# ESP32.net
KiCad netlist of a schematic drawn in Altium Designer
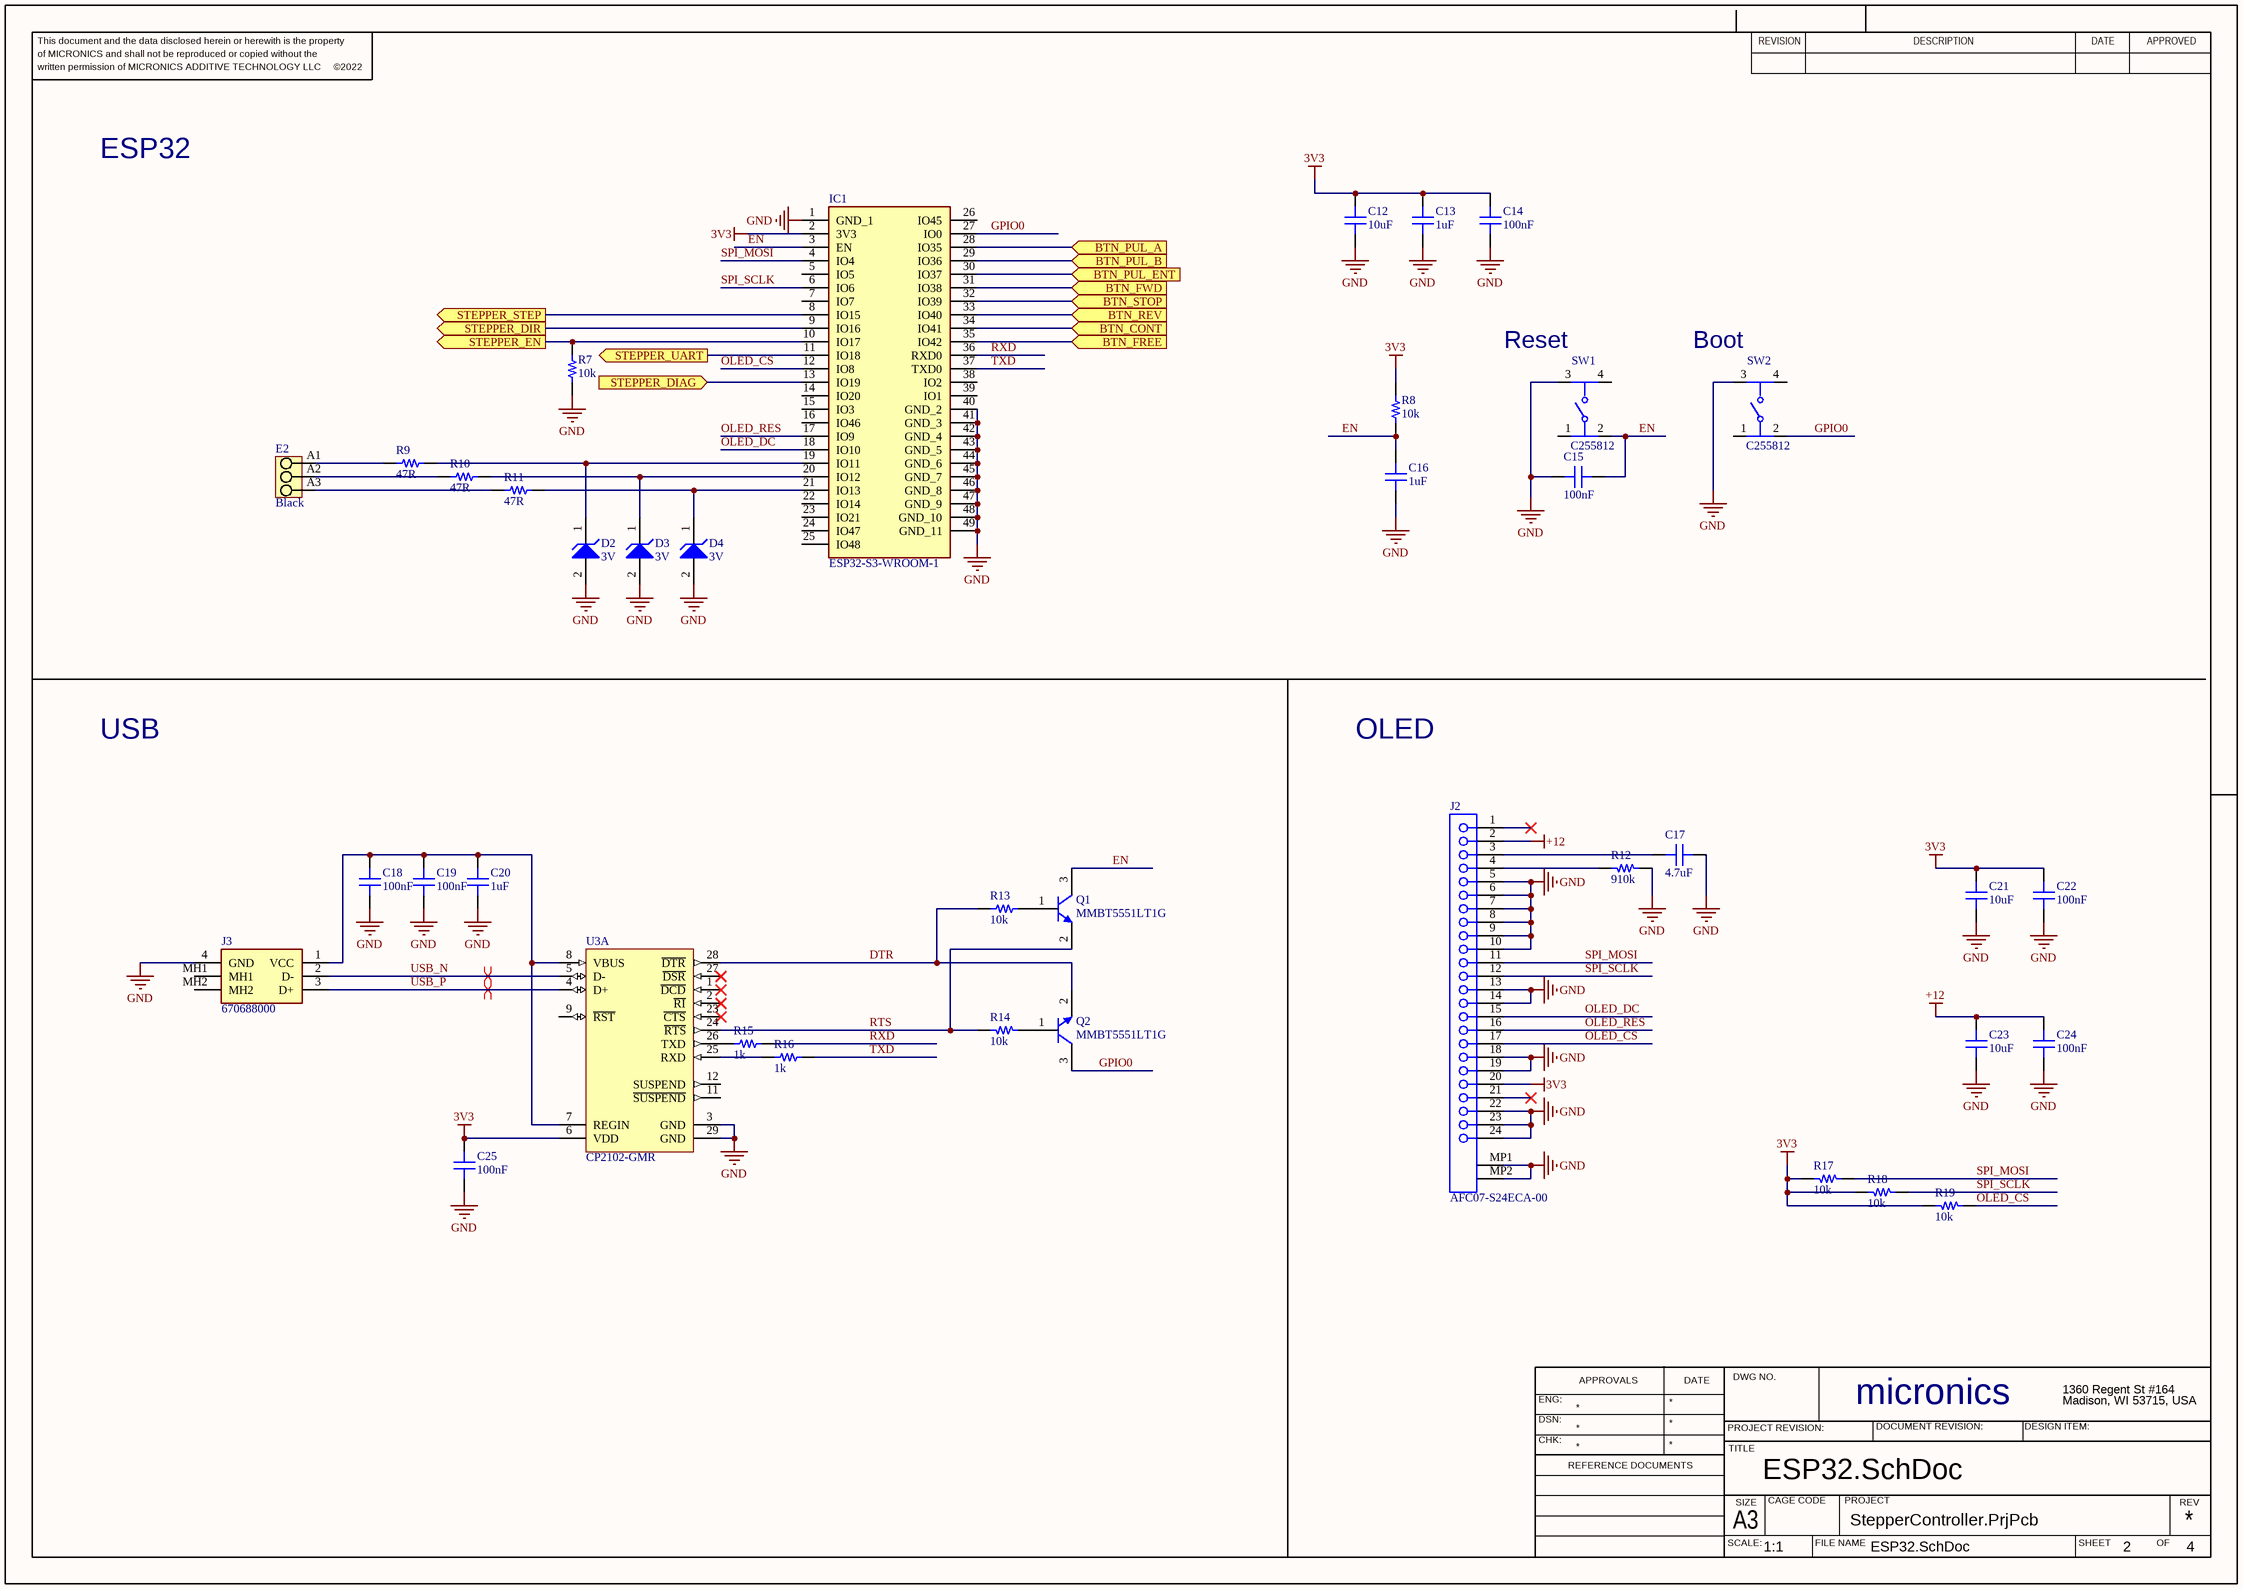
[diagram p0: ESP32.SchDoc]

(export (version "E")
  (design (tool "Eeschema 10.0.6"))
  (components
    (comp (ref "C12")
      (value "10uF")
      (footprint "CAP 1206_3216 - 0.8MM")
      (description "C89632")
      (fields (field (name "PART NUMBER") "MM061A101JCT2A") (field (name "MANUFACTURER") "AVX Corporation"))
      (libsource (lib "Celestial Altium Library - altium_library") (part "Capacitor"))
    )
    (comp (ref "C13")
      (value "1uF")
      (footprint "CAP 0603_1608")
      (description "C15849")
      (fields
        (field (name "PART NUMBER") "250X14W223MV4T")
        (field (name "MANUFACTURER") "Johanson Dielectrics Inc.")
      )
      (libsource (lib "Celestial Altium Library - altium_library") (part "Capacitor"))
    )
    (comp (ref "C14")
      (value "100nF")
      (footprint "CAP 0603_1608")
      (description "C14663")
      (fields
        (field (name "PART NUMBER") "250X14W223MV4T")
        (field (name "MANUFACTURER") "Johanson Dielectrics Inc.")
      )
      (libsource (lib "Celestial Altium Library - altium_library") (part "Capacitor"))
    )
    (comp (ref "C15")
      (value "100nF")
      (footprint "CAP 0603_1608")
      (description "C14663")
      (fields
        (field (name "PART NUMBER") "250X14W223MV4T")
        (field (name "MANUFACTURER") "Johanson Dielectrics Inc.")
      )
      (libsource (lib "Celestial Altium Library - altium_library") (part "Capacitor"))
    )
    (comp (ref "C16")
      (value "1uF")
      (footprint "CAP 0603_1608")
      (description "C15849")
      (fields
        (field (name "PART NUMBER") "250X14W223MV4T")
        (field (name "MANUFACTURER") "Johanson Dielectrics Inc.")
      )
      (libsource (lib "Celestial Altium Library - altium_library") (part "Capacitor"))
    )
    (comp (ref "C17")
      (value "4.7uF")
      (footprint "CAP 1206_3216 - 0.8MM")
      (description "C29823")
      (fields (field (name "PART NUMBER") "MM061A101JCT2A") (field (name "MANUFACTURER") "AVX Corporation"))
      (libsource (lib "Celestial Altium Library - altium_library") (part "Capacitor"))
    )
    (comp (ref "C18")
      (value "100nF")
      (footprint "CAP 0603_1608")
      (description "C14663")
      (fields
        (field (name "PART NUMBER") "250X14W223MV4T")
        (field (name "MANUFACTURER") "Johanson Dielectrics Inc.")
      )
      (libsource (lib "Celestial Altium Library - altium_library") (part "Capacitor"))
    )
    (comp (ref "C19")
      (value "100nF")
      (footprint "CAP 0603_1608")
      (description "C14663")
      (fields
        (field (name "PART NUMBER") "250X14W223MV4T")
        (field (name "MANUFACTURER") "Johanson Dielectrics Inc.")
      )
      (libsource (lib "Celestial Altium Library - altium_library") (part "Capacitor"))
    )
    (comp (ref "C20")
      (value "1uF")
      (footprint "CAP 0603_1608")
      (description "C15849")
      (fields
        (field (name "PART NUMBER") "250X14W223MV4T")
        (field (name "MANUFACTURER") "Johanson Dielectrics Inc.")
      )
      (libsource (lib "Celestial Altium Library - altium_library") (part "Capacitor"))
    )
    (comp (ref "C21")
      (value "10uF")
      (footprint "CAP 1206_3216 - 0.8MM")
      (description "C89632")
      (fields (field (name "PART NUMBER") "MM061A101JCT2A") (field (name "MANUFACTURER") "AVX Corporation"))
      (libsource (lib "Celestial Altium Library - altium_library") (part "Capacitor"))
    )
    (comp (ref "C22")
      (value "100nF")
      (footprint "CAP 0603_1608")
      (description "C14663")
      (fields
        (field (name "PART NUMBER") "250X14W223MV4T")
        (field (name "MANUFACTURER") "Johanson Dielectrics Inc.")
      )
      (libsource (lib "Celestial Altium Library - altium_library") (part "Capacitor"))
    )
    (comp (ref "C23")
      (value "10uF")
      (footprint "CAP 1206_3216 - 0.8MM")
      (description "C89632")
      (fields (field (name "PART NUMBER") "MM061A101JCT2A") (field (name "MANUFACTURER") "AVX Corporation"))
      (libsource (lib "Celestial Altium Library - altium_library") (part "Capacitor"))
    )
    (comp (ref "C24")
      (value "100nF")
      (footprint "CAP 0603_1608")
      (description "C14663")
      (fields
        (field (name "PART NUMBER") "250X14W223MV4T")
        (field (name "MANUFACTURER") "Johanson Dielectrics Inc.")
      )
      (libsource (lib "Celestial Altium Library - altium_library") (part "Capacitor"))
    )
    (comp (ref "C25")
      (value "100nF")
      (footprint "CAP 0603_1608")
      (description "C14663")
      (fields
        (field (name "PART NUMBER") "250X14W223MV4T")
        (field (name "MANUFACTURER") "Johanson Dielectrics Inc.")
      )
      (libsource (lib "Celestial Altium Library - altium_library") (part "Capacitor"))
    )
    (comp (ref "D2")
      (value "3V")
      (footprint "ONSC-SOD-123-2-425-04_V")
      (description "C12756")
      (fields (field (name "PARTNUMBER") "SZMMSZ12T3G") (field (name "MANUFACTURER") "On Semiconductor"))
      (libsource (lib "Altium Content Vault") (part "ONSC-K1A2-2"))
    )
    (comp (ref "D3")
      (value "3V")
      (footprint "ONSC-SOD-123-2-425-04_V")
      (description "C12756")
      (fields (field (name "PARTNUMBER") "SZMMSZ12T3G") (field (name "MANUFACTURER") "On Semiconductor"))
      (libsource (lib "Altium Content Vault") (part "ONSC-K1A2-2"))
    )
    (comp (ref "D4")
      (value "3V")
      (footprint "ONSC-SOD-123-2-425-04_V")
      (description "C12756")
      (fields (field (name "PARTNUMBER") "SZMMSZ12T3G") (field (name "MANUFACTURER") "On Semiconductor"))
      (libsource (lib "Altium Content Vault") (part "ONSC-K1A2-2"))
    )
    (comp (ref "E2")
      (value "Black")
      (footprint "PM_5_08_90_03")
      (description "C430602")
      (fields (field (name "PARTNUMBER") "1760500000") (field (name "MANUFACTURER") "Weidmueller"))
      (libsource (lib "Altium Content Vault") (part "Terminal_03_1x03"))
    )
    (comp (ref "IC1")
      (value "ESP32-S3-WROOM-1")
      (footprint "SamacSys:ESP32S3WROOM1")
      (description "Integrated Circuit")
      (libsource (lib "*") (part "ESP32-S3-WROOM-1"))
    )
    (comp (ref "J2")
      (value "AFC07-S24ECA-00")
      (footprint "MOLX-52437-2471")
      (description "C262643")
      (fields (field (name "PARTNUMBER") "52437-2471") (field (name "MANUFACTURER") "Molex"))
      (libsource (lib "Altium Content Vault") (part "MOLX-52437-2471"))
    )
    (comp (ref "J3")
      (value "670688000")
      (footprint "SamacSys:670688000")
      (description "Connector")
      (fields
        (field (name "MANUFACTURER_PART_NUMBER") "67068-8000")
        (field (name "MOUSER PART NUMBER") "538-67068-8000")
      )
      (libsource (lib "SamacSys") (part "67068-8000"))
    )
    (comp (ref "Q1")
      (value "MMBT5551LT1G")
      (footprint "ONSC-SOT-23-3-318-08_V")
      (description "C41095")
      (fields (field (name "MANUFACTURER") "On Semiconductor"))
      (libsource (lib "Altium Content Vault") (part "ONSC-NPN-B1E2C3-3"))
    )
    (comp (ref "Q2")
      (value "MMBT5551LT1G")
      (footprint "ONSC-SOT-23-3-318-08_V")
      (description "C41095")
      (fields (field (name "MANUFACTURER") "On Semiconductor"))
      (libsource (lib "Altium Content Vault") (part "ONSC-NPN-B1E2C3-3"))
    )
    (comp (ref "R7")
      (value "10k")
      (footprint "RES 0603_1608")
      (description "RES 1% 0603")
      (fields
        (field (name "PART NUMBER") "RNCF0603DTE23K2")
        (field (name "MANUFACTURER") "Stackpole Electronics Inc")
      )
      (libsource (lib "Celestial Altium Library - altium_library") (part "Resistor"))
    )
    (comp (ref "R8")
      (value "10k")
      (footprint "RES 0603_1608")
      (description "RES 1% 0603")
      (fields
        (field (name "PART NUMBER") "RNCF0603DTE23K2")
        (field (name "MANUFACTURER") "Stackpole Electronics Inc")
      )
      (libsource (lib "Celestial Altium Library - altium_library") (part "Resistor"))
    )
    (comp (ref "R9")
      (value "47R")
      (footprint "RES 0603_1608")
      (description "RES 1% 0603")
      (fields
        (field (name "PART NUMBER") "RNCF0603DTE23K2")
        (field (name "MANUFACTURER") "Stackpole Electronics Inc")
      )
      (libsource (lib "Celestial Altium Library - altium_library") (part "Resistor"))
    )
    (comp (ref "R10")
      (value "47R")
      (footprint "RES 0603_1608")
      (description "RES 1% 0603")
      (fields
        (field (name "PART NUMBER") "RNCF0603DTE23K2")
        (field (name "MANUFACTURER") "Stackpole Electronics Inc")
      )
      (libsource (lib "Celestial Altium Library - altium_library") (part "Resistor"))
    )
    (comp (ref "R11")
      (value "47R")
      (footprint "RES 0603_1608")
      (description "RES 1% 0603")
      (fields
        (field (name "PART NUMBER") "RNCF0603DTE23K2")
        (field (name "MANUFACTURER") "Stackpole Electronics Inc")
      )
      (libsource (lib "Celestial Altium Library - altium_library") (part "Resistor"))
    )
    (comp (ref "R12")
      (value "910k")
      (footprint "RES 0603_1608")
      (description "RES 1% 0603")
      (fields
        (field (name "PART NUMBER") "RNCS0603BKE10K0")
        (field (name "MANUFACTURER") "Stackpole Electronics Inc")
      )
      (libsource (lib "Celestial Altium Library - altium_library") (part "Resistor"))
    )
    (comp (ref "R13")
      (value "10k")
      (footprint "RES 0603_1608")
      (description "RES 1% 0603")
      (fields
        (field (name "PART NUMBER") "RNCF0603DTE23K2")
        (field (name "MANUFACTURER") "Stackpole Electronics Inc")
      )
      (libsource (lib "Celestial Altium Library - altium_library") (part "Resistor"))
    )
    (comp (ref "R14")
      (value "10k")
      (footprint "RES 0603_1608")
      (description "RES 1% 0603")
      (fields
        (field (name "PART NUMBER") "RNCF0603DTE23K2")
        (field (name "MANUFACTURER") "Stackpole Electronics Inc")
      )
      (libsource (lib "Celestial Altium Library - altium_library") (part "Resistor"))
    )
    (comp (ref "R15")
      (value "1k")
      (footprint "RES 0603_1608")
      (description "RES 1% 0603")
      (fields
        (field (name "PART NUMBER") "RNCF0603DTE23K2")
        (field (name "MANUFACTURER") "Stackpole Electronics Inc")
      )
      (libsource (lib "Celestial Altium Library - altium_library") (part "Resistor"))
    )
    (comp (ref "R16")
      (value "1k")
      (footprint "RES 0603_1608")
      (description "RES 1% 0603")
      (fields
        (field (name "PART NUMBER") "RNCF0603DTE23K2")
        (field (name "MANUFACTURER") "Stackpole Electronics Inc")
      )
      (libsource (lib "Celestial Altium Library - altium_library") (part "Resistor"))
    )
    (comp (ref "R17")
      (value "10k")
      (footprint "RES 0603_1608")
      (description "RES 1% 0603")
      (fields
        (field (name "PART NUMBER") "RNCF0603DTE23K2")
        (field (name "MANUFACTURER") "Stackpole Electronics Inc")
      )
      (libsource (lib "Celestial Altium Library - altium_library") (part "Resistor"))
    )
    (comp (ref "R18")
      (value "10k")
      (footprint "RES 0603_1608")
      (description "RES 1% 0603")
      (fields
        (field (name "PART NUMBER") "RNCF0603DTE23K2")
        (field (name "MANUFACTURER") "Stackpole Electronics Inc")
      )
      (libsource (lib "Celestial Altium Library - altium_library") (part "Resistor"))
    )
    (comp (ref "R19")
      (value "10k")
      (footprint "RES 0603_1608")
      (description "RES 1% 0603")
      (fields
        (field (name "PART NUMBER") "RNCF0603DTE23K2")
        (field (name "MANUFACTURER") "Stackpole Electronics Inc")
      )
      (libsource (lib "Celestial Altium Library - altium_library") (part "Resistor"))
    )
    (comp (ref "SW1")
      (value "C255812")
      (footprint "FP-FSM2JSMAA-MFG")
      (description "SWITCH TACTILE SPST-NO 0.05A 24V")
      (fields
        (field (name "MANUFACTURER PART NUMBER") "FSM2JSMAA")
        (field (name "MANUFACTURER") "TE Connectivity")
      )
      (libsource (lib "Altium Content Vault") (part "b8895f3f4cefb76e1819d2863dba89b"))
    )
    (comp (ref "SW2")
      (value "C255812")
      (footprint "FP-FSM2JSMAA-MFG")
      (description "SWITCH TACTILE SPST-NO 0.05A 24V")
      (fields
        (field (name "MANUFACTURER PART NUMBER") "FSM2JSMAA")
        (field (name "MANUFACTURER") "TE Connectivity")
      )
      (libsource (lib "Altium Content Vault") (part "b8895f3f4cefb76e1819d2863dba89b"))
    )
    (comp (ref "U3")
      (value "CP2102-GMR")
      (footprint "SLAB-QFN-28-3125x3125TP_M")
      (description "Single-Chip USB to URAT Bridge, 3.3 V, -40 to 85 degC, 28-Pin QFN, RoHS, Tape and Reel")
      (fields (field (name "MANUFACTURER") "Silicon Labs"))
      (libsource (lib "Altium Content Vault") (part "SLAB-CP210X-QFN-28-29"))
    )
  )
  (nets
    (net (code "1") (name "+12") (class "Default")
      (node (ref "C23") (pin "2") (pinfunction "2_2") (pintype "passive"))
      (node (ref "C24") (pin "1") (pinfunction "1_1") (pintype "passive"))
      (node (ref "J2") (pin "2") (pinfunction "2_2") (pintype "passive"))
    )
    (net (code "2") (name "/BTN_CONT") (class "Default")
      (node (ref "IC1") (pin "34") (pinfunction "IO41_34") (pintype "passive"))
    )
    (net (code "3") (name "/BTN_FREE") (class "Default")
      (node (ref "IC1") (pin "35") (pinfunction "IO42_35") (pintype "passive"))
    )
    (net (code "4") (name "/BTN_FWD") (class "Default")
      (node (ref "IC1") (pin "31") (pinfunction "IO38_31") (pintype "passive"))
    )
    (net (code "5") (name "/BTN_PUL_A") (class "Default")
      (node (ref "IC1") (pin "28") (pinfunction "IO35_28") (pintype "passive"))
    )
    (net (code "6") (name "/BTN_PUL_B") (class "Default")
      (node (ref "IC1") (pin "29") (pinfunction "IO36_29") (pintype "passive"))
    )
    (net (code "7") (name "/BTN_PUL_ENT") (class "Default")
      (node (ref "IC1") (pin "30") (pinfunction "IO37_30") (pintype "passive"))
    )
    (net (code "8") (name "/BTN_REV") (class "Default")
      (node (ref "IC1") (pin "33") (pinfunction "IO40_33") (pintype "passive"))
    )
    (net (code "9") (name "/BTN_STOP") (class "Default")
      (node (ref "IC1") (pin "32") (pinfunction "IO39_32") (pintype "passive"))
    )
    (net (code "10") (name "/DTR") (class "Default")
      (node (ref "Q2") (pin "2") (pinfunction "E_2") (pintype "passive"))
      (node (ref "R13") (pin "1") (pinfunction "1_1") (pintype "passive"))
      (node (ref "U3") (pin "28") (pinfunction "~{DTR}_28") (pintype "output"))
    )
    (net (code "11") (name "/EN") (class "Default")
      (node (ref "C15") (pin "1") (pinfunction "1_1") (pintype "passive"))
      (node (ref "C16") (pin "2") (pinfunction "2_2") (pintype "passive"))
      (node (ref "IC1") (pin "3") (pinfunction "EN_3") (pintype "passive"))
      (node (ref "Q1") (pin "3") (pinfunction "C_3") (pintype "passive"))
      (node (ref "R8") (pin "2") (pinfunction "2_2") (pintype "passive"))
      (node (ref "SW1") (pin "2") (pinfunction "2_2") (pintype "passive"))
    )
    (net (code "12") (name "/GPIO0") (class "Default")
      (node (ref "IC1") (pin "27") (pinfunction "IO0_27") (pintype "passive"))
      (node (ref "Q2") (pin "3") (pinfunction "C_3") (pintype "passive"))
      (node (ref "SW2") (pin "2") (pinfunction "2_2") (pintype "passive"))
    )
    (net (code "13") (name "/OLED_CS") (class "Default")
      (node (ref "IC1") (pin "12") (pinfunction "IO8_12") (pintype "passive"))
      (node (ref "J2") (pin "17") (pinfunction "17_17") (pintype "passive"))
      (node (ref "R19") (pin "1") (pinfunction "1_1") (pintype "passive"))
    )
    (net (code "14") (name "/OLED_DC") (class "Default")
      (node (ref "IC1") (pin "18") (pinfunction "IO10_18") (pintype "passive"))
      (node (ref "J2") (pin "15") (pinfunction "15_15") (pintype "passive"))
    )
    (net (code "15") (name "/OLED_RES") (class "Default")
      (node (ref "IC1") (pin "17") (pinfunction "IO9_17") (pintype "passive"))
      (node (ref "J2") (pin "16") (pinfunction "16_16") (pintype "passive"))
    )
    (net (code "16") (name "/RTS") (class "Default")
      (node (ref "Q1") (pin "2") (pinfunction "E_2") (pintype "passive"))
      (node (ref "R14") (pin "1") (pinfunction "1_1") (pintype "passive"))
      (node (ref "U3") (pin "24") (pinfunction "~{RTS}_24") (pintype "output"))
    )
    (net (code "17") (name "/RXD") (class "Default")
      (node (ref "IC1") (pin "36") (pinfunction "RXD0_36") (pintype "passive"))
      (node (ref "R15") (pin "2") (pinfunction "2_2") (pintype "passive"))
    )
    (net (code "18") (name "/SPI_MOSI") (class "Default")
      (node (ref "IC1") (pin "4") (pinfunction "IO4_4") (pintype "passive"))
      (node (ref "J2") (pin "11") (pinfunction "11_11") (pintype "passive"))
      (node (ref "R17") (pin "1") (pinfunction "1_1") (pintype "passive"))
    )
    (net (code "19") (name "/SPI_SCLK") (class "Default")
      (node (ref "IC1") (pin "6") (pinfunction "IO6_6") (pintype "passive"))
      (node (ref "J2") (pin "12") (pinfunction "12_12") (pintype "passive"))
      (node (ref "R18") (pin "1") (pinfunction "1_1") (pintype "passive"))
    )
    (net (code "20") (name "/STEPPER_DIAG") (class "Default")
      (node (ref "IC1") (pin "13") (pinfunction "IO19_13") (pintype "passive"))
    )
    (net (code "21") (name "/STEPPER_DIR") (class "Default")
      (node (ref "IC1") (pin "9") (pinfunction "IO16_9") (pintype "passive"))
    )
    (net (code "22") (name "/STEPPER_EN") (class "Default")
      (node (ref "IC1") (pin "10") (pinfunction "IO17_10") (pintype "passive"))
      (node (ref "R7") (pin "1") (pinfunction "1_1") (pintype "passive"))
    )
    (net (code "23") (name "/STEPPER_STEP") (class "Default")
      (node (ref "IC1") (pin "8") (pinfunction "IO15_8") (pintype "passive"))
    )
    (net (code "24") (name "/STEPPER_UART") (class "Default")
      (node (ref "IC1") (pin "11") (pinfunction "IO18_11") (pintype "passive"))
    )
    (net (code "25") (name "/TXD") (class "Default")
      (node (ref "IC1") (pin "37") (pinfunction "TXD0_37") (pintype "passive"))
      (node (ref "R16") (pin "2") (pinfunction "2_2") (pintype "passive"))
    )
    (net (code "26") (name "/USB_N") (class "Default")
      (node (ref "J3") (pin "2") (pinfunction "D-_2") (pintype "passive"))
      (node (ref "U3") (pin "5") (pinfunction "D-_5") (pintype "bidirectional"))
    )
    (net (code "27") (name "/USB_P") (class "Default")
      (node (ref "J3") (pin "3") (pinfunction "D+_3") (pintype "passive"))
      (node (ref "U3") (pin "4") (pinfunction "D+_4") (pintype "bidirectional"))
    )
    (net (code "28") (name "3V3") (class "Default")
      (node (ref "C12") (pin "2") (pinfunction "2_2") (pintype "passive"))
      (node (ref "C13") (pin "2") (pinfunction "2_2") (pintype "passive"))
      (node (ref "C14") (pin "1") (pinfunction "1_1") (pintype "passive"))
      (node (ref "C21") (pin "2") (pinfunction "2_2") (pintype "passive"))
      (node (ref "C22") (pin "1") (pinfunction "1_1") (pintype "passive"))
      (node (ref "C25") (pin "1") (pinfunction "1_1") (pintype "passive"))
      (node (ref "IC1") (pin "2") (pinfunction "3V3_2") (pintype "passive"))
      (node (ref "J2") (pin "20") (pinfunction "20_20") (pintype "passive"))
      (node (ref "R17") (pin "2") (pinfunction "2_2") (pintype "passive"))
      (node (ref "R18") (pin "2") (pinfunction "2_2") (pintype "passive"))
      (node (ref "R19") (pin "2") (pinfunction "2_2") (pintype "passive"))
      (node (ref "R8") (pin "1") (pinfunction "1_1") (pintype "passive"))
      (node (ref "U3") (pin "6") (pinfunction "VDD_6") (pintype "power_in"))
    )
    (net (code "29") (name "GND") (class "Default")
      (node (ref "C12") (pin "1") (pinfunction "1_1") (pintype "passive"))
      (node (ref "C13") (pin "1") (pinfunction "1_1") (pintype "passive"))
      (node (ref "C14") (pin "2") (pinfunction "2_2") (pintype "passive"))
      (node (ref "C15") (pin "2") (pinfunction "2_2") (pintype "passive"))
      (node (ref "C16") (pin "1") (pinfunction "1_1") (pintype "passive"))
      (node (ref "C17") (pin "1") (pinfunction "1_1") (pintype "passive"))
      (node (ref "C18") (pin "2") (pinfunction "2_2") (pintype "passive"))
      (node (ref "C19") (pin "2") (pinfunction "2_2") (pintype "passive"))
      (node (ref "C20") (pin "1") (pinfunction "1_1") (pintype "passive"))
      (node (ref "C21") (pin "1") (pinfunction "1_1") (pintype "passive"))
      (node (ref "C22") (pin "2") (pinfunction "2_2") (pintype "passive"))
      (node (ref "C23") (pin "1") (pinfunction "1_1") (pintype "passive"))
      (node (ref "C24") (pin "2") (pinfunction "2_2") (pintype "passive"))
      (node (ref "C25") (pin "2") (pinfunction "2_2") (pintype "passive"))
      (node (ref "D2") (pin "2") (pinfunction "A_2") (pintype "passive"))
      (node (ref "D3") (pin "2") (pinfunction "A_2") (pintype "passive"))
      (node (ref "D4") (pin "2") (pinfunction "A_2") (pintype "passive"))
      (node (ref "IC1") (pin "1") (pinfunction "GND_1_1") (pintype "passive"))
      (node (ref "IC1") (pin "40") (pinfunction "GND_2_40") (pintype "passive"))
      (node (ref "IC1") (pin "41") (pinfunction "GND_3_41") (pintype "passive"))
      (node (ref "IC1") (pin "42") (pinfunction "GND_4_42") (pintype "passive"))
      (node (ref "IC1") (pin "43") (pinfunction "GND_5_43") (pintype "passive"))
      (node (ref "IC1") (pin "44") (pinfunction "GND_6_44") (pintype "passive"))
      (node (ref "IC1") (pin "45") (pinfunction "GND_7_45") (pintype "passive"))
      (node (ref "IC1") (pin "46") (pinfunction "GND_8_46") (pintype "passive"))
      (node (ref "IC1") (pin "47") (pinfunction "GND_9_47") (pintype "passive"))
      (node (ref "IC1") (pin "48") (pinfunction "GND_10_48") (pintype "passive"))
      (node (ref "IC1") (pin "49") (pinfunction "GND_11_49") (pintype "passive"))
      (node (ref "J2") (pin "10") (pinfunction "10_10") (pintype "passive"))
      (node (ref "J2") (pin "13") (pinfunction "13_13") (pintype "passive"))
      (node (ref "J2") (pin "14") (pinfunction "14_14") (pintype "passive"))
      (node (ref "J2") (pin "18") (pinfunction "18_18") (pintype "passive"))
      (node (ref "J2") (pin "19") (pinfunction "19_19") (pintype "passive"))
      (node (ref "J2") (pin "22") (pinfunction "22_22") (pintype "passive"))
      (node (ref "J2") (pin "23") (pinfunction "23_23") (pintype "passive"))
      (node (ref "J2") (pin "24") (pinfunction "24_24") (pintype "passive"))
      (node (ref "J2") (pin "5") (pinfunction "5_5") (pintype "passive"))
      (node (ref "J2") (pin "6") (pinfunction "6_6") (pintype "passive"))
      (node (ref "J2") (pin "7") (pinfunction "7_7") (pintype "passive"))
      (node (ref "J2") (pin "8") (pinfunction "8_8") (pintype "passive"))
      (node (ref "J2") (pin "9") (pinfunction "9_9") (pintype "passive"))
      (node (ref "J2") (pin "MP1") (pinfunction "MP1_MP1") (pintype "passive"))
      (node (ref "J2") (pin "MP2") (pinfunction "MP2_MP2") (pintype "passive"))
      (node (ref "J3") (pin "4") (pinfunction "GND_4") (pintype "passive"))
      (node (ref "R12") (pin "2") (pinfunction "2_2") (pintype "passive"))
      (node (ref "R7") (pin "2") (pinfunction "2_2") (pintype "passive"))
      (node (ref "SW1") (pin "3") (pinfunction "3_3") (pintype "passive"))
      (node (ref "SW2") (pin "3") (pinfunction "3_3") (pintype "passive"))
      (node (ref "U3") (pin "29") (pinfunction "GND_29") (pintype "power_in"))
      (node (ref "U3") (pin "3") (pinfunction "GND_3") (pintype "power_in"))
    )
    (net (code "30") (name "Net-(C17-Pad2)") (class "Default")
      (node (ref "C17") (pin "2") (pinfunction "2_2") (pintype "passive"))
      (node (ref "J2") (pin "3") (pinfunction "3_3") (pintype "passive"))
    )
    (net (code "31") (name "Net-(D2-K)") (class "Default")
      (node (ref "D2") (pin "1") (pinfunction "K_1") (pintype "passive"))
      (node (ref "IC1") (pin "19") (pinfunction "IO11_19") (pintype "passive"))
      (node (ref "R9") (pin "2") (pinfunction "2_2") (pintype "passive"))
    )
    (net (code "32") (name "Net-(D3-K)") (class "Default")
      (node (ref "D3") (pin "1") (pinfunction "K_1") (pintype "passive"))
      (node (ref "IC1") (pin "20") (pinfunction "IO12_20") (pintype "passive"))
      (node (ref "R10") (pin "2") (pinfunction "2_2") (pintype "passive"))
    )
    (net (code "33") (name "Net-(D4-K)") (class "Default")
      (node (ref "D4") (pin "1") (pinfunction "K_1") (pintype "passive"))
      (node (ref "IC1") (pin "21") (pinfunction "IO13_21") (pintype "passive"))
      (node (ref "R11") (pin "2") (pinfunction "2_2") (pintype "passive"))
    )
    (net (code "34") (name "Net-(E2-PadA1)") (class "Default")
      (node (ref "E2") (pin "A1") (pinfunction "A1_A1") (pintype "passive"))
      (node (ref "R9") (pin "1") (pinfunction "1_1") (pintype "passive"))
    )
    (net (code "35") (name "Net-(E2-PadA2)") (class "Default")
      (node (ref "E2") (pin "A2") (pinfunction "A2_A2") (pintype "passive"))
      (node (ref "R10") (pin "1") (pinfunction "1_1") (pintype "passive"))
    )
    (net (code "36") (name "Net-(E2-PadA3)") (class "Default")
      (node (ref "E2") (pin "A3") (pinfunction "A3_A3") (pintype "passive"))
      (node (ref "R11") (pin "1") (pinfunction "1_1") (pintype "passive"))
    )
    (net (code "37") (name "Net-(J2-Pad4)") (class "Default")
      (node (ref "J2") (pin "4") (pinfunction "4_4") (pintype "passive"))
      (node (ref "R12") (pin "1") (pinfunction "1_1") (pintype "passive"))
    )
    (net (code "38") (name "Net-(J3-VCC)") (class "Default")
      (node (ref "C18") (pin "1") (pinfunction "1_1") (pintype "passive"))
      (node (ref "C19") (pin "1") (pinfunction "1_1") (pintype "passive"))
      (node (ref "C20") (pin "2") (pinfunction "2_2") (pintype "passive"))
      (node (ref "J3") (pin "1") (pinfunction "VCC_1") (pintype "passive"))
      (node (ref "U3") (pin "7") (pinfunction "REGIN_7") (pintype "power_in"))
      (node (ref "U3") (pin "8") (pinfunction "VBUS_8") (pintype "input"))
    )
    (net (code "39") (name "Net-(Q1-B)") (class "Default")
      (node (ref "Q1") (pin "1") (pinfunction "B_1") (pintype "passive"))
      (node (ref "R13") (pin "2") (pinfunction "2_2") (pintype "passive"))
    )
    (net (code "40") (name "Net-(Q2-B)") (class "Default")
      (node (ref "Q2") (pin "1") (pinfunction "B_1") (pintype "passive"))
      (node (ref "R14") (pin "2") (pinfunction "2_2") (pintype "passive"))
    )
    (net (code "41") (name "Net-(U3A-RXD)") (class "Default")
      (node (ref "R16") (pin "1") (pinfunction "1_1") (pintype "passive"))
      (node (ref "U3") (pin "25") (pinfunction "RXD_25") (pintype "input"))
    )
    (net (code "42") (name "Net-(U3A-TXD)") (class "Default")
      (node (ref "R15") (pin "1") (pinfunction "1_1") (pintype "passive"))
      (node (ref "U3") (pin "26") (pinfunction "TXD_26") (pintype "output"))
    )
    (net (code "43") (name "unconnected-(IC1-IO1-Pad39)") (class "Default")
      (node (ref "IC1") (pin "39") (pinfunction "IO1_39") (pintype "passive"))
    )
    (net (code "44") (name "unconnected-(IC1-IO2-Pad38)") (class "Default")
      (node (ref "IC1") (pin "38") (pinfunction "IO2_38") (pintype "passive"))
    )
    (net (code "45") (name "unconnected-(IC1-IO3-Pad15)") (class "Default")
      (node (ref "IC1") (pin "15") (pinfunction "IO3_15") (pintype "passive"))
    )
    (net (code "46") (name "unconnected-(IC1-IO5-Pad5)") (class "Default")
      (node (ref "IC1") (pin "5") (pinfunction "IO5_5") (pintype "passive"))
    )
    (net (code "47") (name "unconnected-(IC1-IO7-Pad7)") (class "Default")
      (node (ref "IC1") (pin "7") (pinfunction "IO7_7") (pintype "passive"))
    )
    (net (code "48") (name "unconnected-(IC1-IO14-Pad22)") (class "Default")
      (node (ref "IC1") (pin "22") (pinfunction "IO14_22") (pintype "passive"))
    )
    (net (code "49") (name "unconnected-(IC1-IO20-Pad14)") (class "Default")
      (node (ref "IC1") (pin "14") (pinfunction "IO20_14") (pintype "passive"))
    )
    (net (code "50") (name "unconnected-(IC1-IO21-Pad23)") (class "Default")
      (node (ref "IC1") (pin "23") (pinfunction "IO21_23") (pintype "passive"))
    )
    (net (code "51") (name "unconnected-(IC1-IO45-Pad26)") (class "Default")
      (node (ref "IC1") (pin "26") (pinfunction "IO45_26") (pintype "passive"))
    )
    (net (code "52") (name "unconnected-(IC1-IO46-Pad16)") (class "Default")
      (node (ref "IC1") (pin "16") (pinfunction "IO46_16") (pintype "passive"))
    )
    (net (code "53") (name "unconnected-(IC1-IO47-Pad24)") (class "Default")
      (node (ref "IC1") (pin "24") (pinfunction "IO47_24") (pintype "passive"))
    )
    (net (code "54") (name "unconnected-(IC1-IO48-Pad25)") (class "Default")
      (node (ref "IC1") (pin "25") (pinfunction "IO48_25") (pintype "passive"))
    )
    (net (code "55") (name "unconnected-(J2-Pad1)") (class "Default")
      (node (ref "J2") (pin "1") (pinfunction "1_1") (pintype "passive+no_connect"))
    )
    (net (code "56") (name "unconnected-(J2-Pad21)") (class "Default")
      (node (ref "J2") (pin "21") (pinfunction "21_21") (pintype "passive+no_connect"))
    )
    (net (code "57") (name "unconnected-(J3-PadMH1)") (class "Default")
      (node (ref "J3") (pin "MH1") (pinfunction "MH1_MH1") (pintype "passive"))
    )
    (net (code "58") (name "unconnected-(J3-PadMH2)") (class "Default")
      (node (ref "J3") (pin "MH2") (pinfunction "MH2_MH2") (pintype "passive"))
    )
    (net (code "59") (name "unconnected-(SW1-Pad1)") (class "Default")
      (node (ref "SW1") (pin "1") (pinfunction "1_1") (pintype "passive"))
    )
    (net (code "60") (name "unconnected-(SW1-Pad4)") (class "Default")
      (node (ref "SW1") (pin "4") (pinfunction "4_4") (pintype "passive"))
    )
    (net (code "61") (name "unconnected-(SW2-Pad1)") (class "Default")
      (node (ref "SW2") (pin "1") (pinfunction "1_1") (pintype "passive"))
    )
    (net (code "62") (name "unconnected-(SW2-Pad4)") (class "Default")
      (node (ref "SW2") (pin "4") (pinfunction "4_4") (pintype "passive"))
    )
    (net (code "63") (name "unconnected-(U3A-SUSPEND-Pad12)") (class "Default")
      (node (ref "U3") (pin "12") (pinfunction "SUSPEND_12") (pintype "output"))
    )
    (net (code "64") (name "unconnected-(U3A-~{CTS}-Pad23)") (class "Default")
      (node (ref "U3") (pin "23") (pinfunction "~{CTS}_23") (pintype "input+no_connect"))
    )
    (net (code "65") (name "unconnected-(U3A-~{DCD}-Pad1)") (class "Default")
      (node (ref "U3") (pin "1") (pinfunction "~{DCD}_1") (pintype "input+no_connect"))
    )
    (net (code "66") (name "unconnected-(U3A-~{DSR}-Pad27)") (class "Default")
      (node (ref "U3") (pin "27") (pinfunction "~{DSR}_27") (pintype "input+no_connect"))
    )
    (net (code "67") (name "unconnected-(U3A-~{RI}-Pad2)") (class "Default")
      (node (ref "U3") (pin "2") (pinfunction "~{RI}_2") (pintype "input+no_connect"))
    )
    (net (code "68") (name "unconnected-(U3A-~{RST}-Pad9)") (class "Default")
      (node (ref "U3") (pin "9") (pinfunction "~{RST}_9") (pintype "bidirectional"))
    )
    (net (code "69") (name "unconnected-(U3A-~{SUSPEND}-Pad11)") (class "Default")
      (node (ref "U3") (pin "11") (pinfunction "~{SUSPEND}_11") (pintype "output"))
    )
  )
)
